# Power.net
KiCad netlist of a schematic drawn in Altium Designer
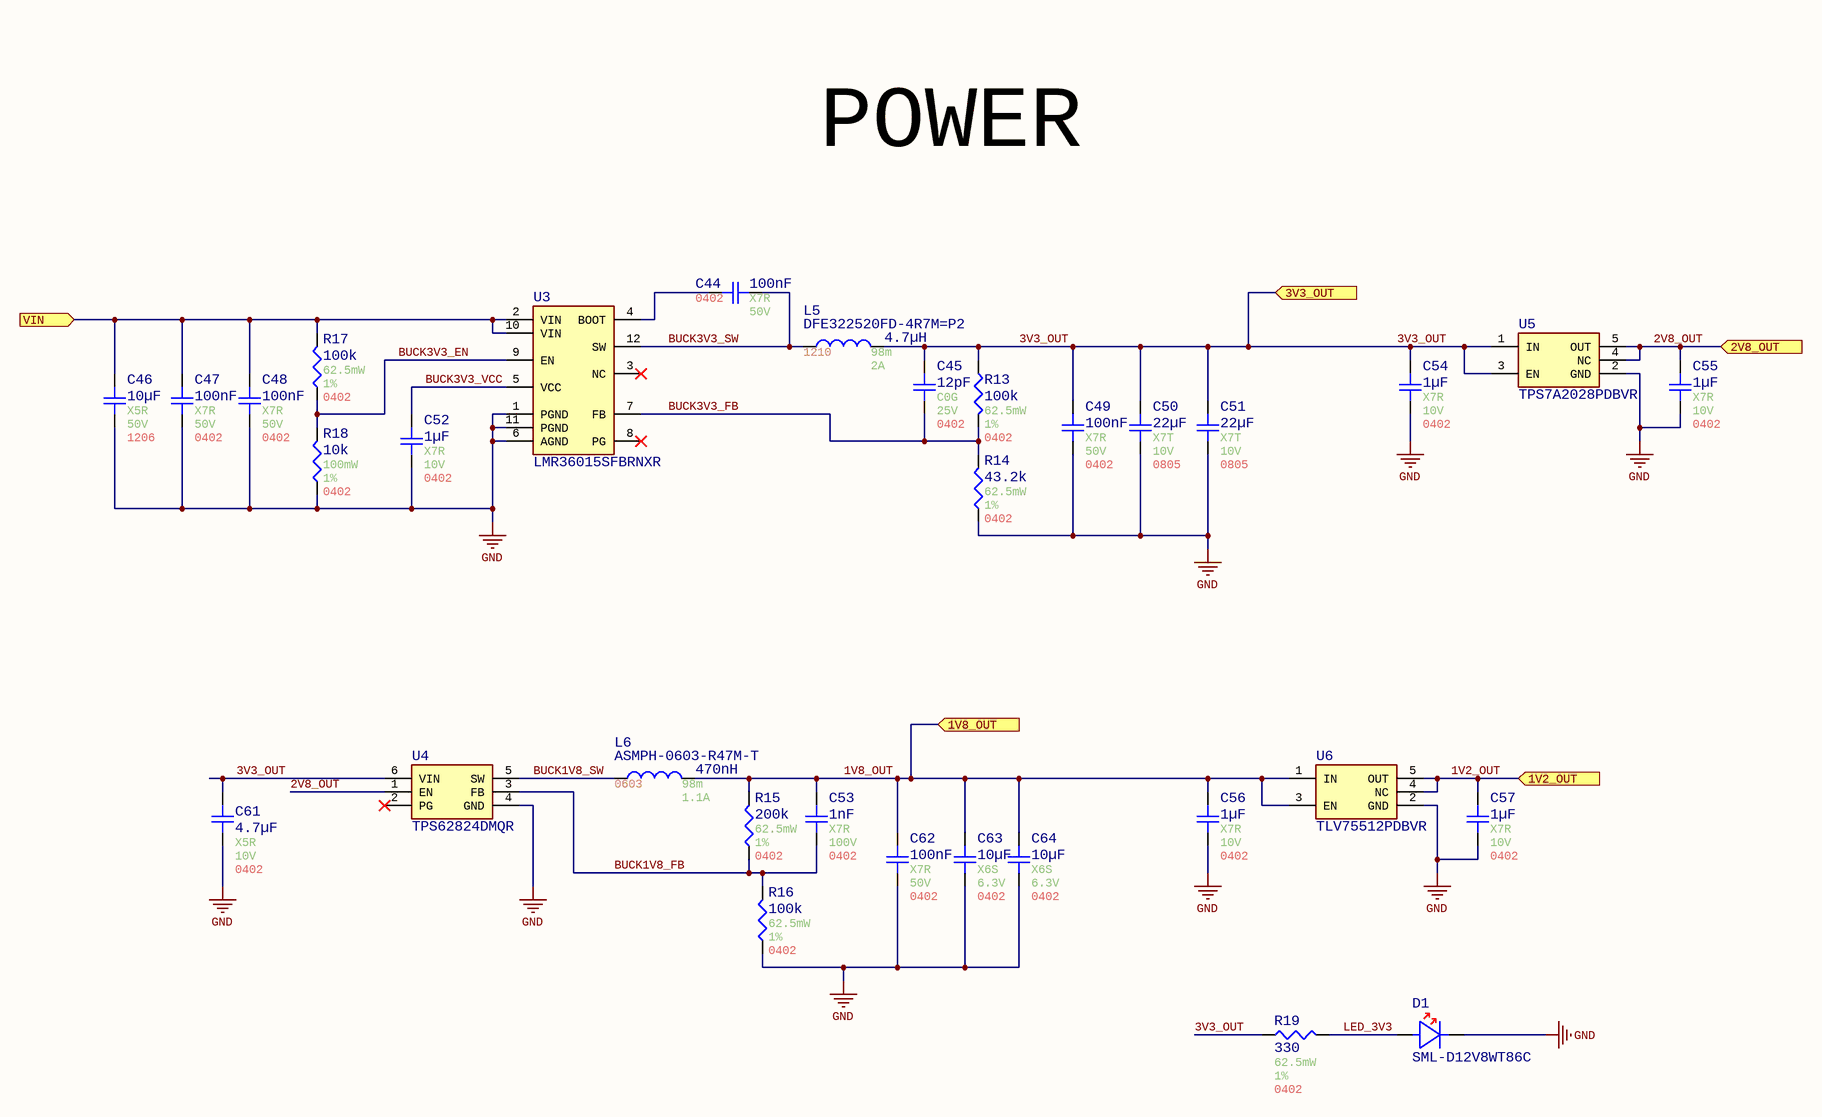
[diagram p0: Power.SchDoc]

(export (version "E")
  (design (tool "Eeschema 10.0.6"))
  (components
    (comp (ref "C44")
      (value "100nF")
      (footprint "Generic 0402 capacitor")
      (fields
        (field (name "TEMPERATURE COEFFICIENT") "X7R")
        (field (name "VOLTAGE RATING") "50V")
        (field (name "CASE/PACKAGE") "0402")
        (field (name "TOLERANCE") "10%")
        (field (name "Comment") "GRT155R71H104KE01D")
      )
      (libsource (lib "Raise Robotics") (part "Unpolarized Capacitor"))
    )
    (comp (ref "C45")
      (value "12pF")
      (footprint "Generic 0402 capacitor")
      (fields
        (field (name "TEMPERATURE COEFFICIENT") "C0G")
        (field (name "VOLTAGE RATING") "25V")
        (field (name "CASE/PACKAGE") "0402")
        (field (name "TOLERANCE") "5%")
        (field (name "Comment") "GRT1555C1E120JA02J")
      )
      (libsource (lib "Raise Robotics") (part "Unpolarized Capacitor"))
    )
    (comp (ref "C46")
      (value "10µF")
      (footprint "Generic 1206 Capacitor")
      (fields
        (field (name "TEMPERATURE COEFFICIENT") "X5R")
        (field (name "VOLTAGE RATING") "50V")
        (field (name "CASE/PACKAGE") "1206")
        (field (name "TOLERANCE") "20%")
        (field (name "Comment") "CL31A106MBHNNNE")
      )
      (libsource (lib "Raise Robotics") (part "Unpolarized Capacitor"))
    )
    (comp (ref "C47")
      (value "100nF")
      (footprint "Generic 0402 capacitor")
      (fields
        (field (name "TEMPERATURE COEFFICIENT") "X7R")
        (field (name "VOLTAGE RATING") "50V")
        (field (name "CASE/PACKAGE") "0402")
        (field (name "TOLERANCE") "10%")
        (field (name "Comment") "GRT155R71H104KE01D")
      )
      (libsource (lib "Raise Robotics") (part "Unpolarized Capacitor"))
    )
    (comp (ref "C48")
      (value "100nF")
      (footprint "Generic 0402 capacitor")
      (fields
        (field (name "TEMPERATURE COEFFICIENT") "X7R")
        (field (name "VOLTAGE RATING") "50V")
        (field (name "CASE/PACKAGE") "0402")
        (field (name "TOLERANCE") "10%")
        (field (name "Comment") "GRT155R71H104KE01D")
      )
      (libsource (lib "Raise Robotics") (part "Unpolarized Capacitor"))
    )
    (comp (ref "C49")
      (value "100nF")
      (footprint "Generic 0402 capacitor")
      (fields
        (field (name "TEMPERATURE COEFFICIENT") "X7R")
        (field (name "VOLTAGE RATING") "50V")
        (field (name "CASE/PACKAGE") "0402")
        (field (name "TOLERANCE") "10%")
        (field (name "Comment") "GRT155R71H104KE01D")
      )
      (libsource (lib "Raise Robotics") (part "Unpolarized Capacitor"))
    )
    (comp (ref "C50")
      (value "22µF")
      (footprint "Generic 0805 Cap")
      (description "22 µF ±20% 10V Ceramic Capacitor X7T 0805 (2012 Metric)")
      (fields
        (field (name "TEMPERATURE COEFFICIENT") "X7T")
        (field (name "VOLTAGE RATING") "10V")
        (field (name "CASE/PACKAGE") "0805")
        (field (name "TOLERANCE") "20%")
        (field (name "Comment") "GRT21BD71A226ME13L")
      )
      (libsource (lib "Raise Robotics") (part "Unpolarized Capacitor"))
    )
    (comp (ref "C51")
      (value "22µF")
      (footprint "Generic 0805 Cap")
      (description "22 µF ±20% 10V Ceramic Capacitor X7T 0805 (2012 Metric)")
      (fields
        (field (name "TEMPERATURE COEFFICIENT") "X7T")
        (field (name "VOLTAGE RATING") "10V")
        (field (name "CASE/PACKAGE") "0805")
        (field (name "TOLERANCE") "20%")
        (field (name "Comment") "GRT21BD71A226ME13L")
      )
      (libsource (lib "Raise Robotics") (part "Unpolarized Capacitor"))
    )
    (comp (ref "C52")
      (value "1µF")
      (footprint "Generic 0402 capacitor")
      (description "Cap Cer 1UF 20V X7T 0402")
      (fields
        (field (name "TEMPERATURE COEFFICIENT") "X7R")
        (field (name "VOLTAGE RATING") "10V")
        (field (name "CASE/PACKAGE") "0402")
        (field (name "TOLERANCE") "20%")
        (field (name "Comment") "MAASL105CD7105MFCA01")
      )
      (libsource (lib "Raise Robotics") (part "Unpolarized Capacitor"))
    )
    (comp (ref "C53")
      (value "1nF")
      (footprint "Generic 0402 capacitor")
      (fields
        (field (name "TEMPERATURE COEFFICIENT") "X7R")
        (field (name "VOLTAGE RATING") "100V")
        (field (name "CASE/PACKAGE") "0402")
        (field (name "TOLERANCE") "10%")
        (field (name "Comment") "GCM155R72A102KA37J")
      )
      (libsource (lib "Raise Robotics") (part "Unpolarized Capacitor"))
    )
    (comp (ref "C54")
      (value "1µF")
      (footprint "Generic 0402 capacitor")
      (description "Cap Cer 1UF 20V X7T 0402")
      (fields
        (field (name "TEMPERATURE COEFFICIENT") "X7R")
        (field (name "VOLTAGE RATING") "10V")
        (field (name "CASE/PACKAGE") "0402")
        (field (name "TOLERANCE") "20%")
        (field (name "Comment") "MAASL105CD7105MFCA01")
      )
      (libsource (lib "Raise Robotics") (part "Unpolarized Capacitor"))
    )
    (comp (ref "C55")
      (value "1µF")
      (footprint "Generic 0402 capacitor")
      (description "Cap Cer 1UF 20V X7T 0402")
      (fields
        (field (name "TEMPERATURE COEFFICIENT") "X7R")
        (field (name "VOLTAGE RATING") "10V")
        (field (name "CASE/PACKAGE") "0402")
        (field (name "TOLERANCE") "20%")
        (field (name "Comment") "MAASL105CD7105MFCA01")
      )
      (libsource (lib "Raise Robotics") (part "Unpolarized Capacitor"))
    )
    (comp (ref "C56")
      (value "1µF")
      (footprint "Generic 0402 capacitor")
      (description "Cap Cer 1UF 20V X7T 0402")
      (fields
        (field (name "TEMPERATURE COEFFICIENT") "X7R")
        (field (name "VOLTAGE RATING") "10V")
        (field (name "CASE/PACKAGE") "0402")
        (field (name "TOLERANCE") "20%")
        (field (name "Comment") "MAASL105CD7105MFCA01")
      )
      (libsource (lib "Raise Robotics") (part "Unpolarized Capacitor"))
    )
    (comp (ref "C57")
      (value "1µF")
      (footprint "Generic 0402 capacitor")
      (description "Cap Cer 1UF 20V X7T 0402")
      (fields
        (field (name "TEMPERATURE COEFFICIENT") "X7R")
        (field (name "VOLTAGE RATING") "10V")
        (field (name "CASE/PACKAGE") "0402")
        (field (name "TOLERANCE") "20%")
        (field (name "Comment") "MAASL105CD7105MFCA01")
      )
      (libsource (lib "Raise Robotics") (part "Unpolarized Capacitor"))
    )
    (comp (ref "C61")
      (value "4.7µF")
      (footprint "Generic 0402 capacitor")
      (fields
        (field (name "TEMPERATURE COEFFICIENT") "X5R")
        (field (name "VOLTAGE RATING") "10V")
        (field (name "CASE/PACKAGE") "0402")
        (field (name "TOLERANCE") "0%")
        (field (name "Comment") "GRT155R61A475ME13D")
      )
      (libsource (lib "Raise Robotics") (part "Unpolarized Capacitor"))
    )
    (comp (ref "C62")
      (value "100nF")
      (footprint "Generic 0402 capacitor")
      (fields
        (field (name "TEMPERATURE COEFFICIENT") "X7R")
        (field (name "VOLTAGE RATING") "50V")
        (field (name "CASE/PACKAGE") "0402")
        (field (name "TOLERANCE") "10%")
        (field (name "Comment") "GRT155R71H104KE01D")
      )
      (libsource (lib "Raise Robotics") (part "Unpolarized Capacitor"))
    )
    (comp (ref "C63")
      (value "10µF")
      (footprint "Generic 0402 capacitor")
      (description "Multilayer Ceramic Capacitors MLCC - SMD/SMT 0402 10uF 6.3VDC 20% X6S AEC-Q200")
      (fields
        (field (name "TEMPERATURE COEFFICIENT") "X6S")
        (field (name "VOLTAGE RATING") "6.3V")
        (field (name "CASE/PACKAGE") "0402")
        (field (name "TOLERANCE") "20%")
        (field (name "Comment") "GRT155C80J106ME13J")
      )
      (libsource (lib "Raise Robotics") (part "Unpolarized Capacitor"))
    )
    (comp (ref "C64")
      (value "10µF")
      (footprint "Generic 0402 capacitor")
      (description "Multilayer Ceramic Capacitors MLCC - SMD/SMT 0402 10uF 6.3VDC 20% X6S AEC-Q200")
      (fields
        (field (name "TEMPERATURE COEFFICIENT") "X6S")
        (field (name "VOLTAGE RATING") "6.3V")
        (field (name "CASE/PACKAGE") "0402")
        (field (name "TOLERANCE") "20%")
        (field (name "Comment") "GRT155C80J106ME13J")
      )
      (libsource (lib "Raise Robotics") (part "Unpolarized Capacitor"))
    )
    (comp (ref "D1")
      (value "SML-D12V8WT86C")
      (footprint "FP-SML-D12-MFG")
      (description "Red 630nm LED Indication - Discrete 2.2V 0603 (1608 Metric)")
      (libsource (lib "Raise Robotics") (part "LED Red"))
    )
    (comp (ref "L5")
      (value "DFE322520FD-4R7M=P2")
      (footprint "FP-DFE322520F_D-IPC_A")
      (description "General Purpose Inductor, 4.7uH, 20%, 1 Element, Metal Alloy-Core, SMD, 1210")
      (fields
        (field (name "DCR") "98m")
        (field (name "CURRENT RATING") "2A")
        (field (name "CASE/PACKAGE") "1210")
        (field (name "ALTIUM_VALUE") "4.7µH")
        (field (name "TOLERANCE") "20%")
      )
      (libsource (lib "Raise Robotics") (part "Generic 2 pin inductor"))
    )
    (comp (ref "L6")
      (value "ASMPH-0603-R47M-T")
      (footprint "0603_1.6x0.8x0.8mm_IND")
      (description "Inductor Power Shielded Multi-Layer 0.47uH 20% 1MHz Ferrite 1.1A 0.19Ohm DCR 0603 T/R")
      (fields
        (field (name "DCR") "98m")
        (field (name "CURRENT RATING") "1.1A")
        (field (name "CASE/PACKAGE") "0603")
        (field (name "ALTIUM_VALUE") "470nH")
        (field (name "TOLERANCE") "20%")
      )
      (libsource (lib "Raise Robotics") (part "Generic 2 pin inductor"))
    )
    (comp (ref "R13")
      (value "100k")
      (footprint "Generic 0402 Resistor")
      (fields
        (field (name "POWER") "62.5mW")
        (field (name "TOLERANCE") "1%")
        (field (name "CASE/PACKAGE") "0402")
        (field (name "MANUFACTURER PART NUMBER") "Blank")
        (field (name "Comment") "WR04X1003FTL")
      )
      (libsource (lib "Raise Robotics") (part "Resistor"))
    )
    (comp (ref "R14")
      (value "43.2k")
      (footprint "Generic 0402 Resistor")
      (description "Fixed Resistor, Metal Glaze/Thick Film, 0.0625W, 43200ohm, 50V, 1% +/-Tol, Surface Mount, 0402")
      (fields
        (field (name "POWER") "62.5mW")
        (field (name "TOLERANCE") "1%")
        (field (name "CASE/PACKAGE") "0402")
        (field (name "Comment") "CR0402-FX-4322GLF")
      )
      (libsource (lib "Raise Robotics") (part "Resistor"))
    )
    (comp (ref "R15")
      (value "200k")
      (footprint "Generic 0402 Resistor")
      (description "Resistor, 200K, 0.1W, Thick Film, 0402;")
      (fields
        (field (name "POWER") "62.5mW")
        (field (name "TOLERANCE") "1%")
        (field (name "CASE/PACKAGE") "0402")
        (field (name "Comment") "560112110041")
      )
      (libsource (lib "Raise Robotics") (part "Resistor"))
    )
    (comp (ref "R16")
      (value "100k")
      (footprint "Generic 0402 Resistor")
      (fields
        (field (name "POWER") "62.5mW")
        (field (name "TOLERANCE") "1%")
        (field (name "CASE/PACKAGE") "0402")
        (field (name "MANUFACTURER PART NUMBER") "Blank")
        (field (name "Comment") "WR04X1003FTL")
      )
      (libsource (lib "Raise Robotics") (part "Resistor"))
    )
    (comp (ref "R17")
      (value "100k")
      (footprint "Generic 0402 Resistor")
      (fields
        (field (name "POWER") "62.5mW")
        (field (name "TOLERANCE") "1%")
        (field (name "CASE/PACKAGE") "0402")
        (field (name "MANUFACTURER PART NUMBER") "Blank")
        (field (name "Comment") "WR04X1003FTL")
      )
      (libsource (lib "Raise Robotics") (part "Resistor"))
    )
    (comp (ref "R18")
      (value "10k")
      (footprint "Generic 0402 Resistor")
      (description "Fixed Resistor, Thin Film, 0.1W, 10000ohm, 50V, 1% +/-Tol, 100ppm/Cel, Surface Mount, 0402")
      (fields
        (field (name "POWER") "100mW")
        (field (name "TOLERANCE") "1%")
        (field (name "CASE/PACKAGE") "0402")
        (field (name "MANUFACTURER PART NUMBER") "Blank")
        (field (name "Comment") "RNCP0402FTD10K0")
      )
      (libsource (lib "Raise Robotics") (part "Resistor"))
    )
    (comp (ref "R19")
      (value "330")
      (footprint "Generic 0402 Resistor")
      (description "Res Thick Film 0402 330 Ohm 1% 0.063W ±100ppm/°C Molded SMD Paper T/R")
      (fields
        (field (name "POWER") "62.5mW")
        (field (name "TOLERANCE") "1%")
        (field (name "CASE/PACKAGE") "0402")
        (field (name "Comment") "RMCF0402FT330R")
      )
      (libsource (lib "Raise Robotics") (part "Resistor"))
    )
    (comp (ref "U3")
      (value "LMR36015SFBRNXR")
      (footprint "VQFN_HR-12_3x2x1.0mm_P0.5mm")
      (libsource (lib "Raise Robotics") (part "LMR36015"))
    )
    (comp (ref "U4")
      (value "TPS62824DMQR")
      (footprint "VSON_HR-6_1.5x1.5x1.0mm_P0.5mm")
      (description "IC REG BUCK ADJ 1A 6VSON Buck Switching Regulator IC Positive Adjustable 0.6V 1 Output 1A 6-VFDFN")
      (libsource (lib "Raise Robotics") (part "TPS62824"))
    )
    (comp (ref "U5")
      (value "TPS7A2028PDBVR")
      (footprint "SOT23-3_3x5x1.1mm_P0.95mm")
      (description "300mA ultra-low-noise low-IQ low-dropout (LDO) linear regulator with high PSRR 5-SOT-23 -40 to 125")
      (libsource (lib "Raise Robotics") (part "TPS7A2028PDBVR"))
    )
    (comp (ref "U6")
      (value "TLV75512PDBVR")
      (footprint "SOT23-3_3x5x1.1mm_P0.95mm")
      (description "500mA high-PSRR low-IQ low-dropout voltage regulator with enable 5-SOT-23 -40 to 125")
      (libsource (lib "Raise Robotics") (part "TPS7A2028PDBVR"))
    )
  )
  (nets
    (net (code "1") (name "/1V2_OUT") (class "Default")
      (node (ref "C57") (pin "2") (pinfunction "2_2") (pintype "passive"))
      (node (ref "U6") (pin "4") (pinfunction "NC_4") (pintype "passive"))
      (node (ref "U6") (pin "5") (pinfunction "OUT_5") (pintype "passive"))
    )
    (net (code "2") (name "/1V8_OUT") (class "Default")
      (node (ref "C53") (pin "2") (pinfunction "2_2") (pintype "passive"))
      (node (ref "C56") (pin "2") (pinfunction "2_2") (pintype "passive"))
      (node (ref "C62") (pin "1") (pinfunction "1_1") (pintype "passive"))
      (node (ref "C63") (pin "2") (pinfunction "2_2") (pintype "passive"))
      (node (ref "C64") (pin "2") (pinfunction "2_2") (pintype "passive"))
      (node (ref "L6") (pin "2") (pinfunction "2_2") (pintype "passive"))
      (node (ref "R15") (pin "2") (pinfunction "2_2") (pintype "passive"))
      (node (ref "U6") (pin "1") (pinfunction "IN_1") (pintype "passive"))
      (node (ref "U6") (pin "3") (pinfunction "EN_3") (pintype "passive"))
    )
    (net (code "3") (name "/2V8_OUT") (class "Default")
      (node (ref "C55") (pin "2") (pinfunction "2_2") (pintype "passive"))
      (node (ref "U4") (pin "1") (pinfunction "EN_1") (pintype "passive"))
      (node (ref "U5") (pin "4") (pinfunction "NC_4") (pintype "passive"))
      (node (ref "U5") (pin "5") (pinfunction "OUT_5") (pintype "passive"))
    )
    (net (code "4") (name "/3V3_OUT") (class "Default")
      (node (ref "C45") (pin "1") (pinfunction "1_1") (pintype "passive"))
      (node (ref "C49") (pin "1") (pinfunction "1_1") (pintype "passive"))
      (node (ref "C50") (pin "2") (pinfunction "2_2") (pintype "passive"))
      (node (ref "C51") (pin "2") (pinfunction "2_2") (pintype "passive"))
      (node (ref "C54") (pin "2") (pinfunction "2_2") (pintype "passive"))
      (node (ref "C61") (pin "1") (pinfunction "1_1") (pintype "passive"))
      (node (ref "L5") (pin "2") (pinfunction "2_2") (pintype "passive"))
      (node (ref "R13") (pin "1") (pinfunction "1_1") (pintype "passive"))
      (node (ref "R19") (pin "1") (pinfunction "1_1") (pintype "passive"))
      (node (ref "U4") (pin "6") (pinfunction "VIN_6") (pintype "passive"))
      (node (ref "U5") (pin "1") (pinfunction "IN_1") (pintype "passive"))
      (node (ref "U5") (pin "3") (pinfunction "EN_3") (pintype "passive"))
    )
    (net (code "5") (name "/BUCK1V8_FB") (class "Default")
      (node (ref "C53") (pin "1") (pinfunction "1_1") (pintype "passive"))
      (node (ref "R15") (pin "1") (pinfunction "1_1") (pintype "passive"))
      (node (ref "R16") (pin "2") (pinfunction "2_2") (pintype "passive"))
      (node (ref "U4") (pin "3") (pinfunction "FB_3") (pintype "passive"))
    )
    (net (code "6") (name "/BUCK1V8_SW") (class "Default")
      (node (ref "L6") (pin "1") (pinfunction "1_1") (pintype "passive"))
      (node (ref "U4") (pin "5") (pinfunction "SW_5") (pintype "passive"))
    )
    (net (code "7") (name "/BUCK3V3_EN") (class "Default")
      (node (ref "R17") (pin "1") (pinfunction "1_1") (pintype "passive"))
      (node (ref "R18") (pin "2") (pinfunction "2_2") (pintype "passive"))
      (node (ref "U3") (pin "9") (pinfunction "EN_9") (pintype "passive"))
    )
    (net (code "8") (name "/BUCK3V3_FB") (class "Default")
      (node (ref "C45") (pin "2") (pinfunction "2_2") (pintype "passive"))
      (node (ref "R13") (pin "2") (pinfunction "2_2") (pintype "passive"))
      (node (ref "R14") (pin "2") (pinfunction "2_2") (pintype "passive"))
      (node (ref "U3") (pin "7") (pinfunction "FB_7") (pintype "passive"))
    )
    (net (code "9") (name "/BUCK3V3_SW") (class "Default")
      (node (ref "C44") (pin "2") (pinfunction "2_2") (pintype "passive"))
      (node (ref "L5") (pin "1") (pinfunction "1_1") (pintype "passive"))
      (node (ref "U3") (pin "12") (pinfunction "SW_12") (pintype "passive"))
    )
    (net (code "10") (name "/BUCK3V3_VCC") (class "Default")
      (node (ref "C52") (pin "2") (pinfunction "2_2") (pintype "passive"))
      (node (ref "U3") (pin "5") (pinfunction "VCC_5") (pintype "passive"))
    )
    (net (code "11") (name "/LED_3V3") (class "Default")
      (node (ref "D1") (pin "2") (pinfunction "A_2") (pintype "passive"))
      (node (ref "R19") (pin "2") (pinfunction "2_2") (pintype "passive"))
    )
    (net (code "12") (name "/VIN") (class "Default")
      (node (ref "C46") (pin "2") (pinfunction "2_2") (pintype "passive"))
      (node (ref "C47") (pin "1") (pinfunction "1_1") (pintype "passive"))
      (node (ref "C48") (pin "1") (pinfunction "1_1") (pintype "passive"))
      (node (ref "R17") (pin "2") (pinfunction "2_2") (pintype "passive"))
      (node (ref "U3") (pin "10") (pinfunction "VIN_10") (pintype "passive"))
      (node (ref "U3") (pin "2") (pinfunction "VIN_2") (pintype "passive"))
    )
    (net (code "13") (name "GND") (class "Default")
      (node (ref "C46") (pin "1") (pinfunction "1_1") (pintype "passive"))
      (node (ref "C47") (pin "2") (pinfunction "2_2") (pintype "passive"))
      (node (ref "C48") (pin "2") (pinfunction "2_2") (pintype "passive"))
      (node (ref "C49") (pin "2") (pinfunction "2_2") (pintype "passive"))
      (node (ref "C50") (pin "1") (pinfunction "1_1") (pintype "passive"))
      (node (ref "C51") (pin "1") (pinfunction "1_1") (pintype "passive"))
      (node (ref "C52") (pin "1") (pinfunction "1_1") (pintype "passive"))
      (node (ref "C54") (pin "1") (pinfunction "1_1") (pintype "passive"))
      (node (ref "C55") (pin "1") (pinfunction "1_1") (pintype "passive"))
      (node (ref "C56") (pin "1") (pinfunction "1_1") (pintype "passive"))
      (node (ref "C57") (pin "1") (pinfunction "1_1") (pintype "passive"))
      (node (ref "C61") (pin "2") (pinfunction "2_2") (pintype "passive"))
      (node (ref "C62") (pin "2") (pinfunction "2_2") (pintype "passive"))
      (node (ref "C63") (pin "1") (pinfunction "1_1") (pintype "passive"))
      (node (ref "C64") (pin "1") (pinfunction "1_1") (pintype "passive"))
      (node (ref "D1") (pin "1") (pinfunction "C_1") (pintype "passive"))
      (node (ref "R14") (pin "1") (pinfunction "1_1") (pintype "passive"))
      (node (ref "R16") (pin "1") (pinfunction "1_1") (pintype "passive"))
      (node (ref "R18") (pin "1") (pinfunction "1_1") (pintype "passive"))
      (node (ref "U3") (pin "1") (pinfunction "PGND_1") (pintype "passive"))
      (node (ref "U3") (pin "11") (pinfunction "PGND_11") (pintype "passive"))
      (node (ref "U3") (pin "6") (pinfunction "AGND_6") (pintype "passive"))
      (node (ref "U4") (pin "4") (pinfunction "GND_4") (pintype "passive"))
      (node (ref "U5") (pin "2") (pinfunction "GND_2") (pintype "passive"))
      (node (ref "U6") (pin "2") (pinfunction "GND_2") (pintype "passive"))
    )
    (net (code "14") (name "Net-(U3-BOOT)") (class "Default")
      (node (ref "C44") (pin "1") (pinfunction "1_1") (pintype "passive"))
      (node (ref "U3") (pin "4") (pinfunction "BOOT_4") (pintype "passive"))
    )
    (net (code "15") (name "unconnected-(U3-NC-Pad3)") (class "Default")
      (node (ref "U3") (pin "3") (pinfunction "NC_3") (pintype "passive+no_connect"))
    )
    (net (code "16") (name "unconnected-(U3-PG-Pad8)") (class "Default")
      (node (ref "U3") (pin "8") (pinfunction "PG_8") (pintype "passive+no_connect"))
    )
    (net (code "17") (name "unconnected-(U4-PG-Pad2)") (class "Default")
      (node (ref "U4") (pin "2") (pinfunction "PG_2") (pintype "passive+no_connect"))
    )
  )
)
